# dam1021.net
KiCad netlist of a schematic drawn in EAGLE
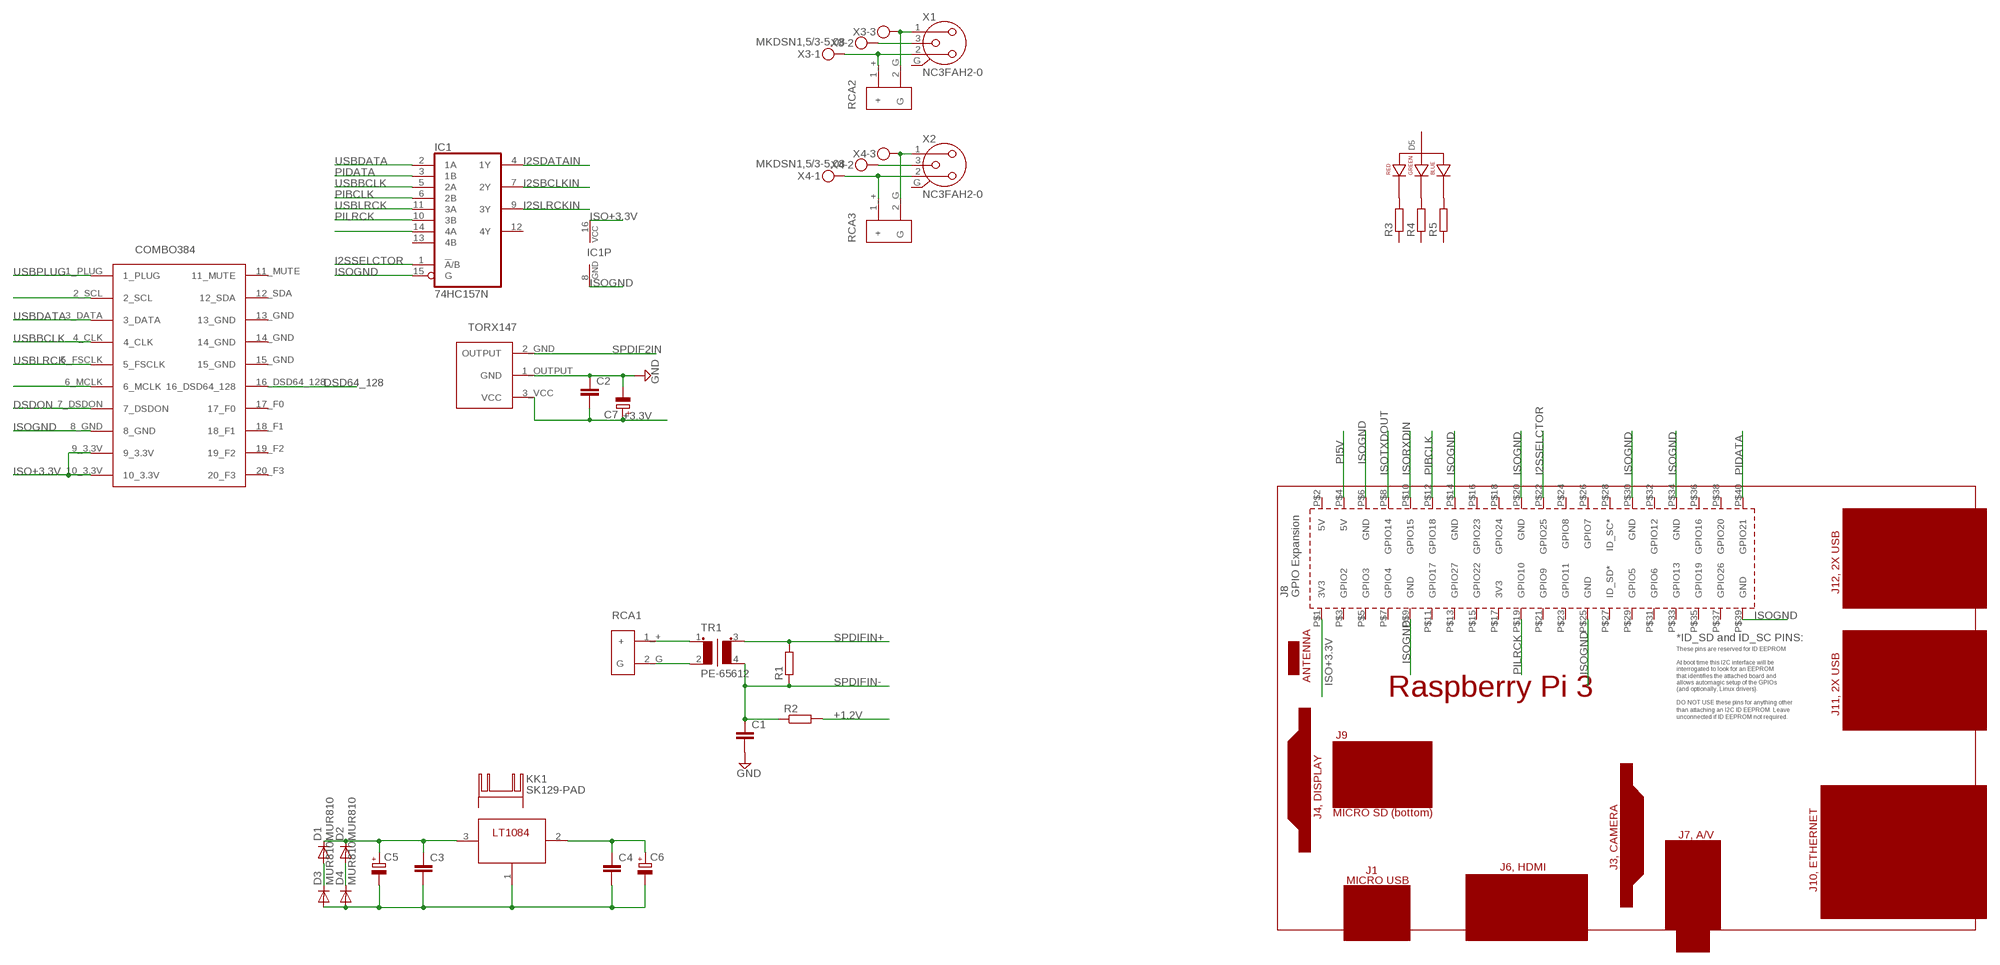
[diagram p0: schematic, sheet 1]
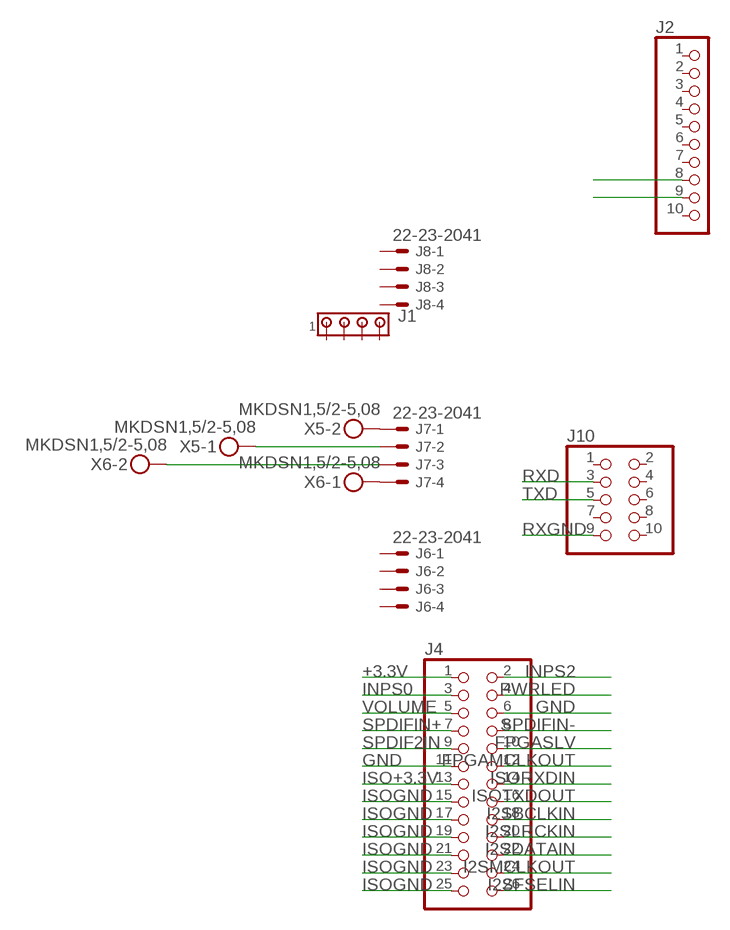
[diagram p1: schematic, sheet 2]

(export (version "E")
  (design (tool "Eeschema 10.0.6"))
  (components
    (comp (ref "J1")
      (value "MTA04-156")
      (footprint "eagle-import:1X4MTA")
      (libsource (lib "eagle-import") (part "MTA04-156"))
    )
    (comp (ref "J2")
      (value "PINHD-1X10")
      (footprint "eagle-import:1X10")
      (libsource (lib "eagle-import") (part "PINHD-1X10"))
    )
    (comp (ref "J4")
      (value "PINHD-2X13")
      (footprint "eagle-import:2X13")
      (libsource (lib "eagle-import") (part "PINHD-2X13"))
    )
    (comp (ref "J6")
      (value "22-23-2041")
      (footprint "eagle-import:22-23-2041")
      (fields (field (name "MF") "MOLEX"))
      (libsource (lib "eagle-import") (part "22-23-2041"))
    )
    (comp (ref "J7")
      (value "22-23-2041")
      (footprint "eagle-import:22-23-2041")
      (fields (field (name "MF") "MOLEX"))
      (libsource (lib "eagle-import") (part "22-23-2041"))
    )
    (comp (ref "J8")
      (value "22-23-2041")
      (footprint "eagle-import:22-23-2041")
      (fields (field (name "MF") "MOLEX"))
      (libsource (lib "eagle-import") (part "22-23-2041"))
    )
    (comp (ref "J10")
      (value "PINHD-2X5")
      (footprint "eagle-import:2X05")
      (libsource (lib "eagle-import") (part "PINHD-2X5"))
    )
    (comp (ref "X5")
      (value "MKDSN1,5/2-5,08")
      (footprint "eagle-import:MKDSN1,5_2-5,08")
      (libsource (lib "eagle-import") (part "MKDSN1,5/2-5,08"))
    )
    (comp (ref "X6")
      (value "MKDSN1,5/2-5,08")
      (footprint "eagle-import:MKDSN1,5_2-5,08")
      (libsource (lib "eagle-import") (part "MKDSN1,5/2-5,08"))
    )
    (comp (ref "C1")
      (value "C-EU050-035X075")
      (footprint "eagle-import:C050-035X075")
      (libsource (lib "eagle-import") (part "C-EU050-035X075"))
    )
    (comp (ref "C2")
      (value "C-EU050-035X075")
      (footprint "eagle-import:C050-035X075")
      (libsource (lib "eagle-import") (part "C-EU050-035X075"))
    )
    (comp (ref "C3")
      (value "C-EU050-035X075")
      (footprint "eagle-import:C050-035X075")
      (libsource (lib "eagle-import") (part "C-EU050-035X075"))
    )
    (comp (ref "C4")
      (value "C-EU050-035X075")
      (footprint "eagle-import:C050-035X075")
      (libsource (lib "eagle-import") (part "C-EU050-035X075"))
    )
    (comp (ref "C5")
      (value "CPOL-EUE7.5-16")
      (footprint "eagle-import:E7,5-16")
      (libsource (lib "eagle-import") (part "CPOL-EUE7.5-16"))
    )
    (comp (ref "C6")
      (value "CPOL-EUE5-10.5")
      (footprint "eagle-import:E5-10,5")
      (libsource (lib "eagle-import") (part "CPOL-EUE5-10.5"))
    )
    (comp (ref "C7")
      (value "CPOL-EUE2.5-7")
      (footprint "eagle-import:E2,5-7")
      (libsource (lib "eagle-import") (part "CPOL-EUE2.5-7"))
    )
    (comp (ref "D1")
      (value "MUR810")
      (footprint "eagle-import:TO220ACS")
      (libsource (lib "eagle-import") (part "MUR810"))
    )
    (comp (ref "D2")
      (value "MUR810")
      (footprint "eagle-import:TO220ACS")
      (libsource (lib "eagle-import") (part "MUR810"))
    )
    (comp (ref "D3")
      (value "MUR810")
      (footprint "eagle-import:TO220ACS")
      (libsource (lib "eagle-import") (part "MUR810"))
    )
    (comp (ref "D4")
      (value "MUR810")
      (footprint "eagle-import:TO220ACS")
      (libsource (lib "eagle-import") (part "MUR810"))
    )
    (comp (ref "D5")
      (value "LED-RGB-CA-THRUCLEAR")
      (footprint "eagle-import:LED-RGB-THRU")
      (libsource (lib "eagle-import") (part "LED-RGB-CA-THRUCLEAR"))
    )
    (comp (ref "IC1")
      (value "74HC157N")
      (footprint "eagle-import:DIL16")
      (libsource (lib "eagle-import") (part "74157NHC"))
    )
    (comp (ref "KK1")
      (value "SK129-PAD")
      (footprint "eagle-import:SK129")
      (libsource (lib "eagle-import") (part "SK129-PAD"))
    )
    (comp (ref "PCB1")
      (value "RPI3")
      (footprint "eagle-import:RPI3")
      (libsource (lib "eagle-import") (part "RPI3"))
    )
    (comp (ref "R1")
      (value "R-EU_0207/10")
      (footprint "eagle-import:0207_10")
      (libsource (lib "eagle-import") (part "R-EU_0207/10"))
    )
    (comp (ref "R2")
      (value "R-EU_0207/10")
      (footprint "eagle-import:0207_10")
      (libsource (lib "eagle-import") (part "R-EU_0207/10"))
    )
    (comp (ref "R3")
      (value "R-EU_0207/10")
      (footprint "eagle-import:0207_10")
      (libsource (lib "eagle-import") (part "R-EU_0207/10"))
    )
    (comp (ref "R4")
      (value "R-EU_0207/10")
      (footprint "eagle-import:0207_10")
      (libsource (lib "eagle-import") (part "R-EU_0207/10"))
    )
    (comp (ref "R5")
      (value "R-EU_0207/10")
      (footprint "eagle-import:0207_10")
      (libsource (lib "eagle-import") (part "R-EU_0207/10"))
    )
    (comp (ref "RCA1")
      (value "RCA")
      (footprint "eagle-import:RCA")
      (libsource (lib "eagle-import") (part "RCA"))
    )
    (comp (ref "RCA2")
      (value "RCA")
      (footprint "eagle-import:RCA")
      (libsource (lib "eagle-import") (part "RCA"))
    )
    (comp (ref "RCA3")
      (value "RCA")
      (footprint "eagle-import:RCA")
      (libsource (lib "eagle-import") (part "RCA"))
    )
    (comp (ref "TR1")
      (value "PE-65612")
      (footprint "eagle-import:PE-65612")
      (libsource (lib "eagle-import") (part "PE-65612"))
    )
    (comp (ref "U$2")
      (value "TORX147")
      (footprint "eagle-import:TORX147")
      (libsource (lib "eagle-import") (part "TORX147"))
    )
    (comp (ref "U$3")
      (value "COMBO384")
      (footprint "eagle-import:COMBO384")
      (libsource (lib "eagle-import") (part "COMBO384"))
    )
    (comp (ref "U$5")
      (value "LT1084")
      (footprint "eagle-import:TO-220")
      (libsource (lib "eagle-import") (part "LT1084"))
    )
    (comp (ref "X1")
      (value "NC3FAH2-0")
      (footprint "eagle-import:NC3FAH2-0")
      (fields (field (name "MPN") "NC3FAH-2-0"))
      (libsource (lib "eagle-import") (part "NC3FAH2-0"))
    )
    (comp (ref "X2")
      (value "NC3FAH2-0")
      (footprint "eagle-import:NC3FAH2-0")
      (fields (field (name "MPN") "NC3FAH-2-0"))
      (libsource (lib "eagle-import") (part "NC3FAH2-0"))
    )
    (comp (ref "X3")
      (value "MKDSN1,5/3-5,08")
      (footprint "eagle-import:MKDSN1,5_3-5,08")
      (libsource (lib "eagle-import") (part "MKDSN1,5/3-5,08"))
    )
    (comp (ref "X4")
      (value "MKDSN1,5/3-5,08")
      (footprint "eagle-import:MKDSN1,5_3-5,08")
      (libsource (lib "eagle-import") (part "MKDSN1,5/3-5,08"))
    )
  )
  (nets
    (net (code "1") (name "+1.2V") (class "Default")
      (node (ref "J2") (pin "9") (pinfunction "9_9") (pintype "passive"))
      (node (ref "R2") (pin "2") (pinfunction "2_2") (pintype "passive"))
    )
    (net (code "2") (name "+3.3V") (class "Default")
      (node (ref "C2") (pin "2") (pinfunction "2_2") (pintype "passive"))
      (node (ref "C7") (pin "+") (pinfunction "+_+") (pintype "passive"))
      (node (ref "J2") (pin "8") (pinfunction "8_8") (pintype "passive"))
      (node (ref "J4") (pin "1") (pinfunction "1_1") (pintype "passive"))
      (node (ref "U$2") (pin "3_VCC") (pinfunction "VCC_3_VCC") (pintype "bidirectional"))
    )
    (net (code "3") (name "AGND") (class "Default")
      (node (ref "J7") (pin "2") (pinfunction "S_2") (pintype "passive"))
      (node (ref "J7") (pin "3") (pinfunction "S_3") (pintype "passive"))
      (node (ref "RCA2") (pin "2_G") (pinfunction "G_2_G") (pintype "bidirectional"))
      (node (ref "RCA3") (pin "2_G") (pinfunction "G_2_G") (pintype "bidirectional"))
      (node (ref "X1") (pin "1") (pinfunction "1_1") (pintype "passive"))
      (node (ref "X2") (pin "1") (pinfunction "1_1") (pintype "passive"))
      (node (ref "X3") (pin "3") (pinfunction "KL_3") (pintype "passive"))
      (node (ref "X4") (pin "3") (pinfunction "KL_3") (pintype "passive"))
      (node (ref "X5") (pin "1") (pinfunction "KL_1") (pintype "passive"))
      (node (ref "X6") (pin "2") (pinfunction "KL_2") (pintype "passive"))
    )
    (net (code "4") (name "DSD64_128") (class "Default")
      (node (ref "U$3") (pin "16_DSD64_128") (pinfunction "16_DSD64_128_16_DSD64_128") (pintype "bidirectional"))
    )
    (net (code "5") (name "DSDON") (class "Default")
      (node (ref "U$3") (pin "7_DSDON") (pinfunction "7_DSDON_7_DSDON") (pintype "bidirectional"))
    )
    (net (code "6") (name "FPGAMCLKOUT") (class "Default")
      (node (ref "J4") (pin "12") (pinfunction "12_12") (pintype "passive"))
    )
    (net (code "7") (name "FPGASLV") (class "Default")
      (node (ref "J4") (pin "10") (pinfunction "10_10") (pintype "passive"))
    )
    (net (code "8") (name "GND") (class "Default")
      (node (ref "C1") (pin "2") (pinfunction "2_2") (pintype "passive"))
      (node (ref "C2") (pin "1") (pinfunction "1_1") (pintype "passive"))
      (node (ref "C7") (pin "-") (pinfunction "-_-") (pintype "passive"))
      (node (ref "J4") (pin "11") (pinfunction "11_11") (pintype "passive"))
      (node (ref "J4") (pin "6") (pinfunction "6_6") (pintype "passive"))
      (node (ref "U$2") (pin "1_OUTPUT") (pinfunction "GND_1_OUTPUT") (pintype "bidirectional"))
    )
    (net (code "9") (name "I2SBCLKIN") (class "Default")
      (node (ref "IC1") (pin "7") (pinfunction "2Y_7") (pintype "output"))
      (node (ref "J4") (pin "18") (pinfunction "18_18") (pintype "passive"))
    )
    (net (code "10") (name "I2SDATAIN") (class "Default")
      (node (ref "IC1") (pin "4") (pinfunction "1Y_4") (pintype "output"))
      (node (ref "J4") (pin "22") (pinfunction "22_22") (pintype "passive"))
    )
    (net (code "11") (name "I2SFSELIN") (class "Default")
      (node (ref "J4") (pin "26") (pinfunction "26_26") (pintype "passive"))
    )
    (net (code "12") (name "I2SLRCKIN") (class "Default")
      (node (ref "IC1") (pin "9") (pinfunction "3Y_9") (pintype "output"))
      (node (ref "J4") (pin "20") (pinfunction "20_20") (pintype "passive"))
    )
    (net (code "13") (name "I2SMCLKOUT") (class "Default")
      (node (ref "J4") (pin "24") (pinfunction "24_24") (pintype "passive"))
    )
    (net (code "14") (name "I2SSELCTOR") (class "Default")
      (node (ref "IC1") (pin "1") (pinfunction "~{A}/B_1") (pintype "input"))
      (node (ref "PCB1") (pin "P$22") (pinfunction "GPIO25_P$22") (pintype "bidirectional"))
    )
    (net (code "15") (name "INPS0") (class "Default")
      (node (ref "J4") (pin "3") (pinfunction "3_3") (pintype "passive"))
    )
    (net (code "16") (name "INPS2") (class "Default")
      (node (ref "J4") (pin "2") (pinfunction "2_2") (pintype "passive"))
    )
    (net (code "17") (name "ISO+3.3V") (class "Default")
      (node (ref "IC1") (pin "16") (pinfunction "VCC_16") (pintype "power_in"))
      (node (ref "J4") (pin "13") (pinfunction "13_13") (pintype "passive"))
      (node (ref "PCB1") (pin "P$1") (pinfunction "3V3_P$1") (pintype "bidirectional"))
      (node (ref "U$3") (pin "10_3.3V") (pinfunction "10_3.3V_10_3.3V") (pintype "bidirectional"))
      (node (ref "U$3") (pin "9_3.3V") (pinfunction "9_3.3V_9_3.3V") (pintype "bidirectional"))
    )
    (net (code "18") (name "ISOGND") (class "Default")
      (node (ref "C3") (pin "2") (pinfunction "2_2") (pintype "passive"))
      (node (ref "C4") (pin "2") (pinfunction "2_2") (pintype "passive"))
      (node (ref "C5") (pin "-") (pinfunction "-_-") (pintype "passive"))
      (node (ref "C6") (pin "-") (pinfunction "-_-") (pintype "passive"))
      (node (ref "D3") (pin "A") (pinfunction "A_A") (pintype "passive"))
      (node (ref "D4") (pin "A") (pinfunction "A_A") (pintype "passive"))
      (node (ref "IC1") (pin "15") (pinfunction "G_15") (pintype "input"))
      (node (ref "IC1") (pin "8") (pinfunction "GND_8") (pintype "power_in"))
      (node (ref "J4") (pin "15") (pinfunction "15_15") (pintype "passive"))
      (node (ref "J4") (pin "17") (pinfunction "17_17") (pintype "passive"))
      (node (ref "J4") (pin "19") (pinfunction "19_19") (pintype "passive"))
      (node (ref "J4") (pin "21") (pinfunction "21_21") (pintype "passive"))
      (node (ref "J4") (pin "23") (pinfunction "23_23") (pintype "passive"))
      (node (ref "J4") (pin "25") (pinfunction "25_25") (pintype "passive"))
      (node (ref "PCB1") (pin "P$14") (pinfunction "GND_P$14") (pintype "bidirectional"))
      (node (ref "PCB1") (pin "P$20") (pinfunction "GND_P$20") (pintype "bidirectional"))
      (node (ref "PCB1") (pin "P$25") (pinfunction "GND_P$25") (pintype "bidirectional"))
      (node (ref "PCB1") (pin "P$30") (pinfunction "GND_P$30") (pintype "bidirectional"))
      (node (ref "PCB1") (pin "P$34") (pinfunction "GND_P$34") (pintype "bidirectional"))
      (node (ref "PCB1") (pin "P$39") (pinfunction "GND_P$39") (pintype "bidirectional"))
      (node (ref "PCB1") (pin "P$6") (pinfunction "GND_P$6") (pintype "bidirectional"))
      (node (ref "PCB1") (pin "P$9") (pinfunction "GND_P$9") (pintype "bidirectional"))
      (node (ref "U$3") (pin "8_GND") (pinfunction "8_GND_8_GND") (pintype "bidirectional"))
      (node (ref "U$5") (pin "1") (pinfunction "P$1_1") (pintype "bidirectional"))
    )
    (net (code "19") (name "ISORXDIN") (class "Default")
      (node (ref "J4") (pin "14") (pinfunction "14_14") (pintype "passive"))
      (node (ref "PCB1") (pin "P$10") (pinfunction "GPIO15_P$10") (pintype "bidirectional"))
    )
    (net (code "20") (name "ISOTXDOUT") (class "Default")
      (node (ref "J4") (pin "16") (pinfunction "16_16") (pintype "passive"))
      (node (ref "PCB1") (pin "P$8") (pinfunction "GPIO14_P$8") (pintype "bidirectional"))
    )
    (net (code "21") (name "Net-(D1-PadA)") (class "Default")
      (node (ref "D1") (pin "A") (pinfunction "A_A") (pintype "passive"))
      (node (ref "D3") (pin "C") (pinfunction "C_C") (pintype "passive"))
    )
    (net (code "22") (name "Net-(D2-PadA)") (class "Default")
      (node (ref "D2") (pin "A") (pinfunction "A_A") (pintype "passive"))
      (node (ref "D4") (pin "C") (pinfunction "C_C") (pintype "passive"))
    )
    (net (code "23") (name "Net-(D5-BLUE_CATHODE)") (class "Default")
      (node (ref "D5") (pin "4") (pinfunction "BLUE_CATHODE_4") (pintype "bidirectional"))
      (node (ref "R5") (pin "2") (pinfunction "2_2") (pintype "passive"))
    )
    (net (code "24") (name "Net-(D5-GREEN_CATHODE)") (class "Default")
      (node (ref "D5") (pin "3") (pinfunction "GREEN_CATHODE_3") (pintype "bidirectional"))
      (node (ref "R4") (pin "2") (pinfunction "2_2") (pintype "passive"))
    )
    (net (code "25") (name "Net-(D5-RED_CATHODE)") (class "Default")
      (node (ref "D5") (pin "1") (pinfunction "RED_CATHODE_1") (pintype "bidirectional"))
      (node (ref "R3") (pin "2") (pinfunction "2_2") (pintype "passive"))
    )
    (net (code "26") (name "Net-(J7A-S)") (class "Default")
      (node (ref "J7") (pin "1") (pinfunction "S_1") (pintype "passive"))
      (node (ref "X5") (pin "2") (pinfunction "KL_2") (pintype "passive"))
    )
    (net (code "27") (name "Net-(J7D-S)") (class "Default")
      (node (ref "J7") (pin "4") (pinfunction "S_4") (pintype "passive"))
      (node (ref "X6") (pin "1") (pinfunction "KL_1") (pintype "passive"))
    )
    (net (code "28") (name "Net-(RCA1-+)") (class "Default")
      (node (ref "RCA1") (pin "1_+") (pinfunction "+_1_+") (pintype "bidirectional"))
      (node (ref "TR1") (pin "1") (pinfunction "1_1") (pintype "passive"))
    )
    (net (code "29") (name "Net-(RCA1-G)") (class "Default")
      (node (ref "RCA1") (pin "2_G") (pinfunction "G_2_G") (pintype "bidirectional"))
      (node (ref "TR1") (pin "2") (pinfunction "3_2") (pintype "passive"))
    )
    (net (code "30") (name "Net-(RCA2-+)") (class "Default")
      (node (ref "RCA2") (pin "1_+") (pinfunction "+_1_+") (pintype "bidirectional"))
      (node (ref "X1") (pin "2") (pinfunction "2_2") (pintype "passive"))
      (node (ref "X3") (pin "1") (pinfunction "KL_1") (pintype "passive"))
    )
    (net (code "31") (name "Net-(RCA3-+)") (class "Default")
      (node (ref "RCA3") (pin "1_+") (pinfunction "+_1_+") (pintype "bidirectional"))
      (node (ref "X2") (pin "2") (pinfunction "2_2") (pintype "passive"))
      (node (ref "X4") (pin "1") (pinfunction "KL_1") (pintype "passive"))
    )
    (net (code "32") (name "Net-(U$5-P$3)") (class "Default")
      (node (ref "C3") (pin "1") (pinfunction "1_1") (pintype "passive"))
      (node (ref "C5") (pin "+") (pinfunction "+_+") (pintype "passive"))
      (node (ref "D1") (pin "C") (pinfunction "C_C") (pintype "passive"))
      (node (ref "D2") (pin "C") (pinfunction "C_C") (pintype "passive"))
      (node (ref "U$5") (pin "3") (pinfunction "P$3_3") (pintype "input"))
    )
    (net (code "33") (name "Net-(X3B-KL)") (class "Default")
      (node (ref "X1") (pin "3") (pinfunction "3_3") (pintype "passive"))
      (node (ref "X3") (pin "2") (pinfunction "KL_2") (pintype "passive"))
    )
    (net (code "34") (name "Net-(X4B-KL)") (class "Default")
      (node (ref "X2") (pin "3") (pinfunction "3_3") (pintype "passive"))
      (node (ref "X4") (pin "2") (pinfunction "KL_2") (pintype "passive"))
    )
    (net (code "35") (name "PI5V") (class "Default")
      (node (ref "C4") (pin "1") (pinfunction "1_1") (pintype "passive"))
      (node (ref "C6") (pin "+") (pinfunction "+_+") (pintype "passive"))
      (node (ref "PCB1") (pin "P$4") (pinfunction "5V_P$4") (pintype "bidirectional"))
      (node (ref "U$5") (pin "2") (pinfunction "P$2_2") (pintype "output"))
    )
    (net (code "36") (name "PIBCLK") (class "Default")
      (node (ref "IC1") (pin "6") (pinfunction "2B_6") (pintype "input"))
      (node (ref "PCB1") (pin "P$12") (pinfunction "GPIO18_P$12") (pintype "bidirectional"))
    )
    (net (code "37") (name "PIDATA") (class "Default")
      (node (ref "IC1") (pin "3") (pinfunction "1B_3") (pintype "input"))
      (node (ref "PCB1") (pin "P$40") (pinfunction "GPIO21_P$40") (pintype "bidirectional"))
    )
    (net (code "38") (name "PILRCK") (class "Default")
      (node (ref "IC1") (pin "10") (pinfunction "3B_10") (pintype "input"))
      (node (ref "PCB1") (pin "P$19") (pinfunction "GPIO10_P$19") (pintype "bidirectional"))
    )
    (net (code "39") (name "PWRLED") (class "Default")
      (node (ref "J4") (pin "4") (pinfunction "4_4") (pintype "passive"))
    )
    (net (code "40") (name "RXD") (class "Default")
      (node (ref "J10") (pin "3") (pinfunction "3_3") (pintype "passive"))
    )
    (net (code "41") (name "RXGND") (class "Default")
      (node (ref "J10") (pin "9") (pinfunction "9_9") (pintype "passive"))
    )
    (net (code "42") (name "SPDIF2IN") (class "Default")
      (node (ref "J4") (pin "9") (pinfunction "9_9") (pintype "passive"))
      (node (ref "U$2") (pin "2_GND") (pinfunction "OUTPUT_2_GND") (pintype "bidirectional"))
    )
    (net (code "43") (name "SPDIFIN+") (class "Default")
      (node (ref "J4") (pin "7") (pinfunction "7_7") (pintype "passive"))
      (node (ref "R1") (pin "2") (pinfunction "2_2") (pintype "passive"))
      (node (ref "TR1") (pin "3") (pinfunction "6_3") (pintype "passive"))
    )
    (net (code "44") (name "SPDIFIN-") (class "Default")
      (node (ref "C1") (pin "1") (pinfunction "1_1") (pintype "passive"))
      (node (ref "J4") (pin "8") (pinfunction "8_8") (pintype "passive"))
      (node (ref "R1") (pin "1") (pinfunction "1_1") (pintype "passive"))
      (node (ref "R2") (pin "1") (pinfunction "1_1") (pintype "passive"))
      (node (ref "TR1") (pin "4") (pinfunction "4_4") (pintype "passive"))
    )
    (net (code "45") (name "TXD") (class "Default")
      (node (ref "J10") (pin "5") (pinfunction "5_5") (pintype "passive"))
    )
    (net (code "46") (name "USBBCLK") (class "Default")
      (node (ref "IC1") (pin "5") (pinfunction "2A_5") (pintype "input"))
      (node (ref "U$3") (pin "4_CLK") (pinfunction "4_CLK_4_CLK") (pintype "bidirectional"))
    )
    (net (code "47") (name "USBDATA") (class "Default")
      (node (ref "IC1") (pin "2") (pinfunction "1A_2") (pintype "input"))
      (node (ref "U$3") (pin "3_DATA") (pinfunction "3_DATA_3_DATA") (pintype "bidirectional"))
    )
    (net (code "48") (name "USBLRCK") (class "Default")
      (node (ref "IC1") (pin "11") (pinfunction "3A_11") (pintype "input"))
      (node (ref "U$3") (pin "5_FSCLK") (pinfunction "5_FSCLK_5_FSCLK") (pintype "bidirectional"))
    )
    (net (code "49") (name "USBPLUG") (class "Default")
      (node (ref "U$3") (pin "1_PLUG") (pinfunction "1_PLUG_1_PLUG") (pintype "bidirectional"))
    )
    (net (code "50") (name "VOLUME") (class "Default")
      (node (ref "J4") (pin "5") (pinfunction "5_5") (pintype "passive"))
    )
    (net (code "51") (name "unconnected-(D5-ANODE-Pad2)") (class "Default")
      (node (ref "D5") (pin "2") (pinfunction "ANODE_2") (pintype "bidirectional"))
    )
    (net (code "52") (name "unconnected-(IC1A-4A-Pad14)") (class "Default")
      (node (ref "IC1") (pin "14") (pinfunction "4A_14") (pintype "input"))
    )
    (net (code "53") (name "unconnected-(IC1A-4B-Pad13)") (class "Default")
      (node (ref "IC1") (pin "13") (pinfunction "4B_13") (pintype "input"))
    )
    (net (code "54") (name "unconnected-(IC1A-4Y-Pad12)") (class "Default")
      (node (ref "IC1") (pin "12") (pinfunction "4Y_12") (pintype "output"))
    )
    (net (code "55") (name "unconnected-(J1-Pad1)") (class "Default")
      (node (ref "J1") (pin "1") (pinfunction "1_1") (pintype "passive"))
    )
    (net (code "56") (name "unconnected-(J1-Pad2)") (class "Default")
      (node (ref "J1") (pin "2") (pinfunction "2_2") (pintype "passive"))
    )
    (net (code "57") (name "unconnected-(J1-Pad3)") (class "Default")
      (node (ref "J1") (pin "3") (pinfunction "3_3") (pintype "passive"))
    )
    (net (code "58") (name "unconnected-(J1-Pad4)") (class "Default")
      (node (ref "J1") (pin "4") (pinfunction "4_4") (pintype "passive"))
    )
    (net (code "59") (name "unconnected-(J2-Pad1)") (class "Default")
      (node (ref "J2") (pin "1") (pinfunction "1_1") (pintype "passive"))
    )
    (net (code "60") (name "unconnected-(J2-Pad2)") (class "Default")
      (node (ref "J2") (pin "2") (pinfunction "2_2") (pintype "passive"))
    )
    (net (code "61") (name "unconnected-(J2-Pad3)") (class "Default")
      (node (ref "J2") (pin "3") (pinfunction "3_3") (pintype "passive"))
    )
    (net (code "62") (name "unconnected-(J2-Pad4)") (class "Default")
      (node (ref "J2") (pin "4") (pinfunction "4_4") (pintype "passive"))
    )
    (net (code "63") (name "unconnected-(J2-Pad5)") (class "Default")
      (node (ref "J2") (pin "5") (pinfunction "5_5") (pintype "passive"))
    )
    (net (code "64") (name "unconnected-(J2-Pad6)") (class "Default")
      (node (ref "J2") (pin "6") (pinfunction "6_6") (pintype "passive"))
    )
    (net (code "65") (name "unconnected-(J2-Pad7)") (class "Default")
      (node (ref "J2") (pin "7") (pinfunction "7_7") (pintype "passive"))
    )
    (net (code "66") (name "unconnected-(J2-Pad10)") (class "Default")
      (node (ref "J2") (pin "10") (pinfunction "10_10") (pintype "passive"))
    )
    (net (code "67") (name "unconnected-(J6A-S-Pad1)") (class "Default")
      (node (ref "J6") (pin "1") (pinfunction "S_1") (pintype "passive"))
    )
    (net (code "68") (name "unconnected-(J6B-S-Pad2)") (class "Default")
      (node (ref "J6") (pin "2") (pinfunction "S_2") (pintype "passive"))
    )
    (net (code "69") (name "unconnected-(J6C-S-Pad3)") (class "Default")
      (node (ref "J6") (pin "3") (pinfunction "S_3") (pintype "passive"))
    )
    (net (code "70") (name "unconnected-(J6D-S-Pad4)") (class "Default")
      (node (ref "J6") (pin "4") (pinfunction "S_4") (pintype "passive"))
    )
    (net (code "71") (name "unconnected-(J8A-S-Pad1)") (class "Default")
      (node (ref "J8") (pin "1") (pinfunction "S_1") (pintype "passive"))
    )
    (net (code "72") (name "unconnected-(J8B-S-Pad2)") (class "Default")
      (node (ref "J8") (pin "2") (pinfunction "S_2") (pintype "passive"))
    )
    (net (code "73") (name "unconnected-(J8C-S-Pad3)") (class "Default")
      (node (ref "J8") (pin "3") (pinfunction "S_3") (pintype "passive"))
    )
    (net (code "74") (name "unconnected-(J8D-S-Pad4)") (class "Default")
      (node (ref "J8") (pin "4") (pinfunction "S_4") (pintype "passive"))
    )
    (net (code "75") (name "unconnected-(J10-Pad1)") (class "Default")
      (node (ref "J10") (pin "1") (pinfunction "1_1") (pintype "passive"))
    )
    (net (code "76") (name "unconnected-(J10-Pad2)") (class "Default")
      (node (ref "J10") (pin "2") (pinfunction "2_2") (pintype "passive"))
    )
    (net (code "77") (name "unconnected-(J10-Pad4)") (class "Default")
      (node (ref "J10") (pin "4") (pinfunction "4_4") (pintype "passive"))
    )
    (net (code "78") (name "unconnected-(J10-Pad6)") (class "Default")
      (node (ref "J10") (pin "6") (pinfunction "6_6") (pintype "passive"))
    )
    (net (code "79") (name "unconnected-(J10-Pad7)") (class "Default")
      (node (ref "J10") (pin "7") (pinfunction "7_7") (pintype "passive"))
    )
    (net (code "80") (name "unconnected-(J10-Pad8)") (class "Default")
      (node (ref "J10") (pin "8") (pinfunction "8_8") (pintype "passive"))
    )
    (net (code "81") (name "unconnected-(J10-Pad10)") (class "Default")
      (node (ref "J10") (pin "10") (pinfunction "10_10") (pintype "passive"))
    )
    (net (code "82") (name "unconnected-(KK1-K-PadA2,5)") (class "Default")
      (node (ref "KK1") (pin "A2,5") (pinfunction "K_A2,5") (pintype "passive"))
    )
    (net (code "83") (name "unconnected-(KK1-K-PadB2,5)") (class "Default")
      (node (ref "KK1") (pin "B2,5") (pinfunction "K_B2,5") (pintype "passive"))
    )
    (net (code "84") (name "unconnected-(PCB1-3V3-PadP$17)") (class "Default")
      (node (ref "PCB1") (pin "P$17") (pinfunction "3V3_P$17") (pintype "bidirectional"))
    )
    (net (code "85") (name "unconnected-(PCB1-5V-PadP$2)") (class "Default")
      (node (ref "PCB1") (pin "P$2") (pinfunction "5V_P$2") (pintype "bidirectional"))
    )
    (net (code "86") (name "unconnected-(PCB1-GPIO2-PadP$3)") (class "Default")
      (node (ref "PCB1") (pin "P$3") (pinfunction "GPIO2_P$3") (pintype "bidirectional"))
    )
    (net (code "87") (name "unconnected-(PCB1-GPIO3-PadP$5)") (class "Default")
      (node (ref "PCB1") (pin "P$5") (pinfunction "GPIO3_P$5") (pintype "bidirectional"))
    )
    (net (code "88") (name "unconnected-(PCB1-GPIO4-PadP$7)") (class "Default")
      (node (ref "PCB1") (pin "P$7") (pinfunction "GPIO4_P$7") (pintype "bidirectional"))
    )
    (net (code "89") (name "unconnected-(PCB1-GPIO5-PadP$29)") (class "Default")
      (node (ref "PCB1") (pin "P$29") (pinfunction "GPIO5_P$29") (pintype "bidirectional"))
    )
    (net (code "90") (name "unconnected-(PCB1-GPIO6-PadP$31)") (class "Default")
      (node (ref "PCB1") (pin "P$31") (pinfunction "GPIO6_P$31") (pintype "bidirectional"))
    )
    (net (code "91") (name "unconnected-(PCB1-GPIO7-PadP$26)") (class "Default")
      (node (ref "PCB1") (pin "P$26") (pinfunction "GPIO7_P$26") (pintype "bidirectional"))
    )
    (net (code "92") (name "unconnected-(PCB1-GPIO8-PadP$24)") (class "Default")
      (node (ref "PCB1") (pin "P$24") (pinfunction "GPIO8_P$24") (pintype "bidirectional"))
    )
    (net (code "93") (name "unconnected-(PCB1-GPIO9-PadP$21)") (class "Default")
      (node (ref "PCB1") (pin "P$21") (pinfunction "GPIO9_P$21") (pintype "bidirectional"))
    )
    (net (code "94") (name "unconnected-(PCB1-GPIO11-PadP$23)") (class "Default")
      (node (ref "PCB1") (pin "P$23") (pinfunction "GPIO11_P$23") (pintype "bidirectional"))
    )
    (net (code "95") (name "unconnected-(PCB1-GPIO12-PadP$32)") (class "Default")
      (node (ref "PCB1") (pin "P$32") (pinfunction "GPIO12_P$32") (pintype "bidirectional"))
    )
    (net (code "96") (name "unconnected-(PCB1-GPIO13-PadP$33)") (class "Default")
      (node (ref "PCB1") (pin "P$33") (pinfunction "GPIO13_P$33") (pintype "bidirectional"))
    )
    (net (code "97") (name "unconnected-(PCB1-GPIO16-PadP$36)") (class "Default")
      (node (ref "PCB1") (pin "P$36") (pinfunction "GPIO16_P$36") (pintype "bidirectional"))
    )
    (net (code "98") (name "unconnected-(PCB1-GPIO17-PadP$11)") (class "Default")
      (node (ref "PCB1") (pin "P$11") (pinfunction "GPIO17_P$11") (pintype "bidirectional"))
    )
    (net (code "99") (name "unconnected-(PCB1-GPIO19-PadP$35)") (class "Default")
      (node (ref "PCB1") (pin "P$35") (pinfunction "GPIO19_P$35") (pintype "bidirectional"))
    )
    (net (code "100") (name "unconnected-(PCB1-GPIO20-PadP$38)") (class "Default")
      (node (ref "PCB1") (pin "P$38") (pinfunction "GPIO20_P$38") (pintype "bidirectional"))
    )
    (net (code "101") (name "unconnected-(PCB1-GPIO22-PadP$15)") (class "Default")
      (node (ref "PCB1") (pin "P$15") (pinfunction "GPIO22_P$15") (pintype "bidirectional"))
    )
    (net (code "102") (name "unconnected-(PCB1-GPIO23-PadP$16)") (class "Default")
      (node (ref "PCB1") (pin "P$16") (pinfunction "GPIO23_P$16") (pintype "bidirectional"))
    )
    (net (code "103") (name "unconnected-(PCB1-GPIO24-PadP$18)") (class "Default")
      (node (ref "PCB1") (pin "P$18") (pinfunction "GPIO24_P$18") (pintype "bidirectional"))
    )
    (net (code "104") (name "unconnected-(PCB1-GPIO26-PadP$37)") (class "Default")
      (node (ref "PCB1") (pin "P$37") (pinfunction "GPIO26_P$37") (pintype "bidirectional"))
    )
    (net (code "105") (name "unconnected-(PCB1-GPIO27-PadP$13)") (class "Default")
      (node (ref "PCB1") (pin "P$13") (pinfunction "GPIO27_P$13") (pintype "bidirectional"))
    )
    (net (code "106") (name "unconnected-(PCB1-ID_SC*-PadP$28)") (class "Default")
      (node (ref "PCB1") (pin "P$28") (pinfunction "ID_SC*_P$28") (pintype "bidirectional"))
    )
    (net (code "107") (name "unconnected-(PCB1-ID_SD*-PadP$27)") (class "Default")
      (node (ref "PCB1") (pin "P$27") (pinfunction "ID_SD*_P$27") (pintype "bidirectional"))
    )
    (net (code "108") (name "unconnected-(R3-Pad1)") (class "Default")
      (node (ref "R3") (pin "1") (pinfunction "1_1") (pintype "passive"))
    )
    (net (code "109") (name "unconnected-(R4-Pad1)") (class "Default")
      (node (ref "R4") (pin "1") (pinfunction "1_1") (pintype "passive"))
    )
    (net (code "110") (name "unconnected-(R5-Pad1)") (class "Default")
      (node (ref "R5") (pin "1") (pinfunction "1_1") (pintype "passive"))
    )
    (net (code "111") (name "unconnected-(U$3-Pad2_SCL)") (class "Default")
      (node (ref "U$3") (pin "2_SCL") (pinfunction "2_SCL_2_SCL") (pintype "bidirectional"))
    )
    (net (code "112") (name "unconnected-(U$3-Pad6_MCLK)") (class "Default")
      (node (ref "U$3") (pin "6_MCLK") (pinfunction "6_MCLK_6_MCLK") (pintype "bidirectional"))
    )
    (net (code "113") (name "unconnected-(U$3-Pad11_MUTE)") (class "Default")
      (node (ref "U$3") (pin "11_MUTE") (pinfunction "11_MUTE_11_MUTE") (pintype "bidirectional"))
    )
    (net (code "114") (name "unconnected-(U$3-Pad12_SDA)") (class "Default")
      (node (ref "U$3") (pin "12_SDA") (pinfunction "12_SDA_12_SDA") (pintype "bidirectional"))
    )
    (net (code "115") (name "unconnected-(U$3-Pad13_GND)") (class "Default")
      (node (ref "U$3") (pin "13_GND") (pinfunction "13_GND_13_GND") (pintype "bidirectional"))
    )
    (net (code "116") (name "unconnected-(U$3-Pad14_GND)") (class "Default")
      (node (ref "U$3") (pin "14_GND") (pinfunction "14_GND_14_GND") (pintype "bidirectional"))
    )
    (net (code "117") (name "unconnected-(U$3-Pad15_GND)") (class "Default")
      (node (ref "U$3") (pin "15_GND") (pinfunction "15_GND_15_GND") (pintype "bidirectional"))
    )
    (net (code "118") (name "unconnected-(U$3-Pad17_F0)") (class "Default")
      (node (ref "U$3") (pin "17_F0") (pinfunction "17_F0_17_F0") (pintype "bidirectional"))
    )
    (net (code "119") (name "unconnected-(U$3-Pad18_F1)") (class "Default")
      (node (ref "U$3") (pin "18_F1") (pinfunction "18_F1_18_F1") (pintype "bidirectional"))
    )
    (net (code "120") (name "unconnected-(U$3-Pad19_F2)") (class "Default")
      (node (ref "U$3") (pin "19_F2") (pinfunction "19_F2_19_F2") (pintype "bidirectional"))
    )
    (net (code "121") (name "unconnected-(U$3-Pad20_F3)") (class "Default")
      (node (ref "U$3") (pin "20_F3") (pinfunction "20_F3_20_F3") (pintype "bidirectional"))
    )
    (net (code "122") (name "unconnected-(X1-PadG)") (class "Default")
      (node (ref "X1") (pin "G") (pinfunction "G_G") (pintype "passive"))
    )
    (net (code "123") (name "unconnected-(X2-PadG)") (class "Default")
      (node (ref "X2") (pin "G") (pinfunction "G_G") (pintype "passive"))
    )
  )
)
